# IMD.net
KiCad netlist of a schematic drawn in Altium Designer
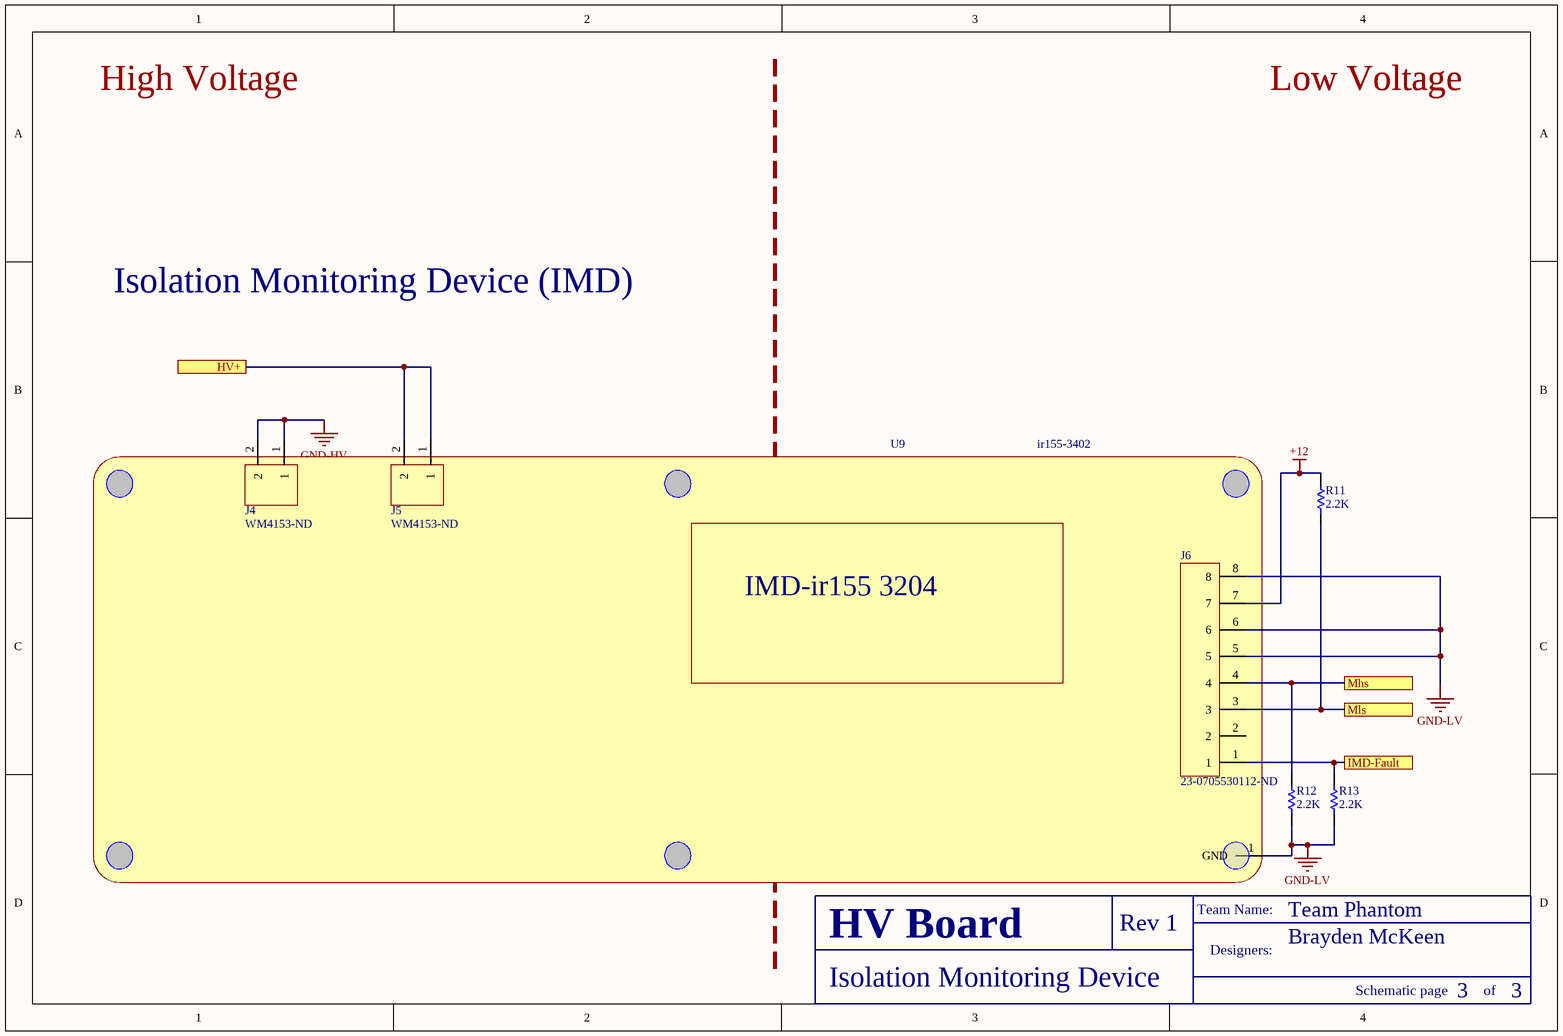
[diagram p0: IMD.SchDoc]

(export (version "E")
  (design (tool "Eeschema 10.0.6"))
  (components
    (comp (ref "J4")
      (value "WM4153-ND")
      (footprint "2PIN")
      (description "CONN HEADER R/A 2POS 2.54MM")
      (fields (field (name "MANUFACTURER") "Molex") (field (name "MANUFACTURER PART NUMBER") "0705530106"))
      (libsource (lib "Connectors") (part "2PIN"))
    )
    (comp (ref "J5")
      (value "WM4153-ND")
      (footprint "2PIN")
      (description "CONN HEADER R/A 2POS 2.54MM")
      (fields (field (name "MANUFACTURER") "Molex") (field (name "MANUFACTURER PART NUMBER") "0705530106"))
      (libsource (lib "Connectors") (part "2PIN"))
    )
    (comp (ref "J6")
      (value "23-0705530112-ND")
      (footprint "8PIN")
      (description "CONN HEADER R/A 8POS 2.54MM")
      (fields (field (name "MANUFACTURER") "Molex") (field (name "MANUFACTURER PART NUMBER") "70553-0112"))
      (libsource (lib "Connectors") (part "8PIN"))
    )
    (comp (ref "R11")
      (value "2.2K")
      (footprint "RES-0805")
      (description "RES SMD 2.2K OHM 1% 1/8W 0805")
      (fields
        (field (name "MANUFACTURER") "Yageo")
        (field (name "MANUFACTURER PART NUMBER") "RC0805FR-072K2L")
      )
      (libsource (lib "Resistors") (part "0805-2.2KR"))
    )
    (comp (ref "R12")
      (value "2.2K")
      (footprint "RES-0805")
      (description "RES SMD 2.2K OHM 1% 1/8W 0805")
      (fields
        (field (name "MANUFACTURER") "Yageo")
        (field (name "MANUFACTURER PART NUMBER") "RC0805FR-072K2L")
      )
      (libsource (lib "Resistors") (part "0805-2.2KR"))
    )
    (comp (ref "R13")
      (value "2.2K")
      (footprint "RES-0805")
      (description "RES SMD 2.2K OHM 1% 1/8W 0805")
      (fields
        (field (name "MANUFACTURER") "Yageo")
        (field (name "MANUFACTURER PART NUMBER") "RC0805FR-072K2L")
      )
      (libsource (lib "") (part "0805-2.2KR_1"))
    )
    (comp (ref "U9")
      (value "ir155-3402")
      (footprint "IMD-Bender ir155 3204")
      (description "ISOMETER iso-F1 IR155-3204")
      (libsource (lib "Misc") (part "IMD-ir155-3402"))
    )
  )
  (nets
    (net (code "1") (name "+12") (class "Default")
      (node (ref "J6") (pin "7") (pinfunction "7_7") (pintype "passive"))
      (node (ref "R11") (pin "2") (pinfunction "2_2") (pintype "passive"))
    )
    (net (code "2") (name "/HV+") (class "Default")
      (node (ref "J5") (pin "1") (pinfunction "1_1") (pintype "passive"))
      (node (ref "J5") (pin "2") (pinfunction "2_2") (pintype "passive"))
    )
    (net (code "3") (name "/IMD-Fault") (class "Default")
      (node (ref "J6") (pin "1") (pinfunction "1_1") (pintype "passive"))
      (node (ref "R13") (pin "2") (pinfunction "2_2") (pintype "passive"))
    )
    (net (code "4") (name "/Mhs") (class "Default")
      (node (ref "J6") (pin "4") (pinfunction "4_4") (pintype "passive"))
      (node (ref "R12") (pin "2") (pinfunction "2_2") (pintype "passive"))
    )
    (net (code "5") (name "/Mls") (class "Default")
      (node (ref "J6") (pin "3") (pinfunction "3_3") (pintype "passive"))
      (node (ref "R11") (pin "1") (pinfunction "1_1") (pintype "passive"))
    )
    (net (code "6") (name "GND-HV") (class "Default")
      (node (ref "J4") (pin "1") (pinfunction "1_1") (pintype "passive"))
      (node (ref "J4") (pin "2") (pinfunction "2_2") (pintype "passive"))
    )
    (net (code "7") (name "GND-LV") (class "Default")
      (node (ref "J6") (pin "5") (pinfunction "5_5") (pintype "passive"))
      (node (ref "J6") (pin "6") (pinfunction "6_6") (pintype "passive"))
      (node (ref "J6") (pin "8") (pinfunction "8_8") (pintype "passive"))
      (node (ref "R12") (pin "1") (pinfunction "1_1") (pintype "passive"))
      (node (ref "R13") (pin "1") (pinfunction "1_1") (pintype "passive"))
      (node (ref "U9") (pin "1") (pinfunction "GND_1") (pintype "passive"))
    )
    (net (code "8") (name "unconnected-(J6-Pad2)") (class "Default")
      (node (ref "J6") (pin "2") (pinfunction "2_2") (pintype "passive"))
    )
  )
)
